# Front-end.net
KiCad netlist of a schematic drawn in Altium Designer
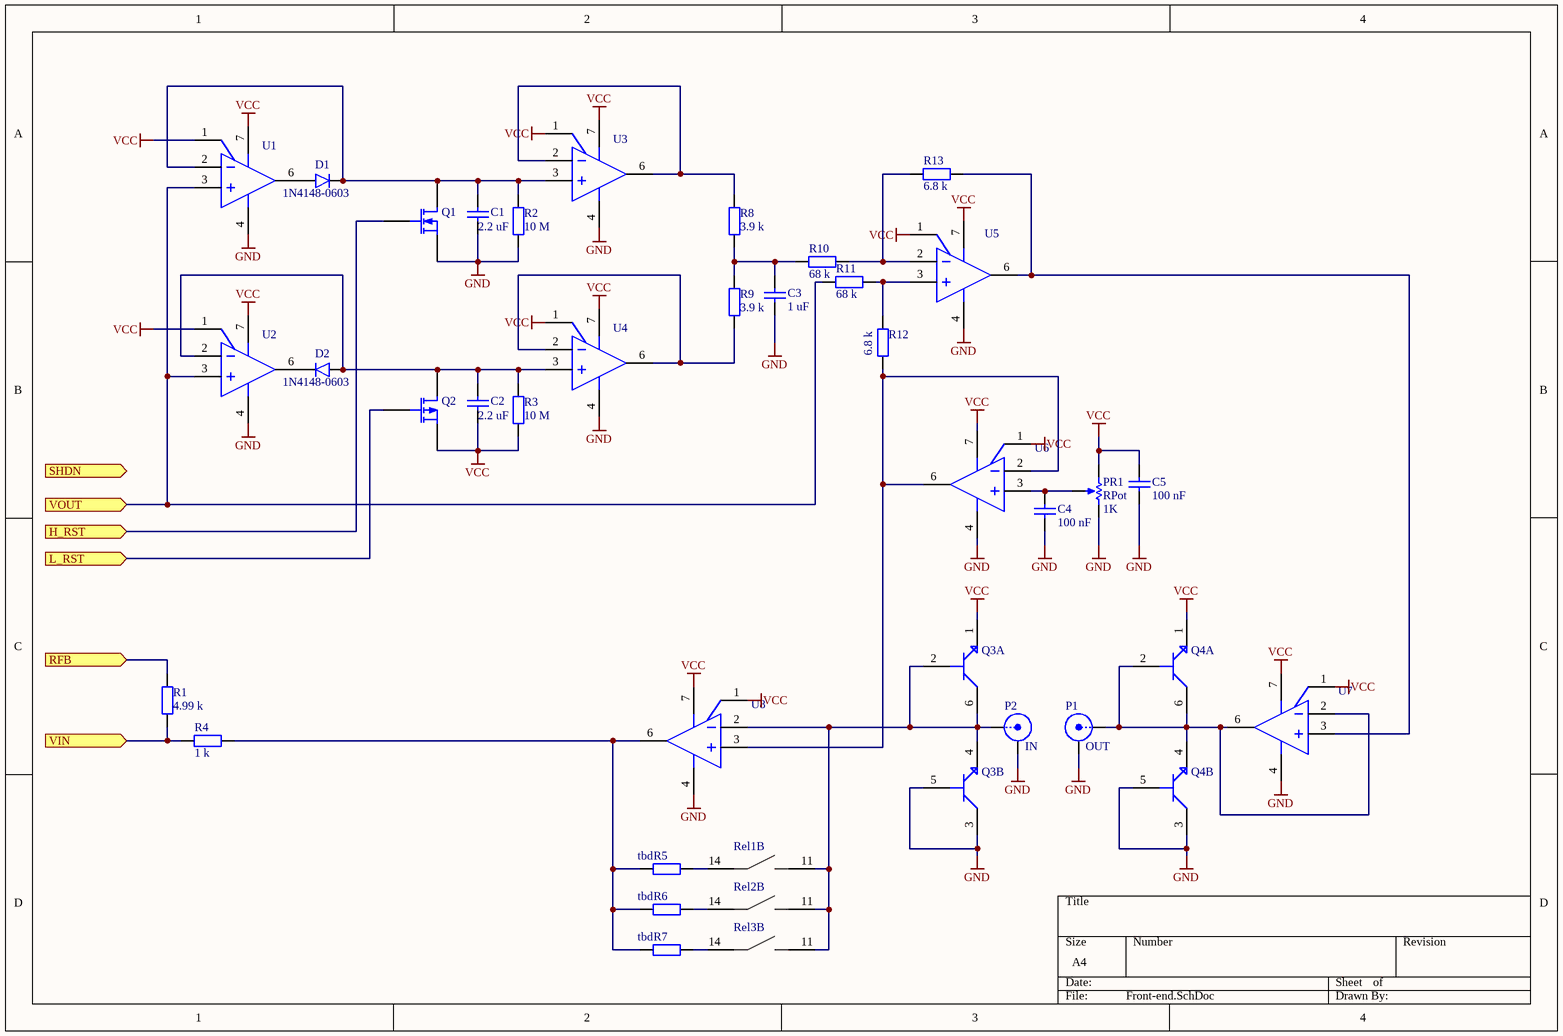
[diagram p0: Front-end.SchDoc]

(export (version "E")
  (design (tool "Eeschema 10.0.6"))
  (components
    (comp (ref "C1")
      (value "2.2 uF")
      (footprint "C1206")
      (description "Capacitor (Semiconductor SIM Model)")
      (fields (field (name "PUBLISHER") "Altium Limited"))
      (libsource (lib "Miscellaneous Devices") (part "Cap Semi"))
    )
    (comp (ref "C2")
      (value "2.2 uF")
      (footprint "C1206")
      (description "Capacitor (Semiconductor SIM Model)")
      (fields (field (name "PUBLISHER") "Altium Limited"))
      (libsource (lib "Miscellaneous Devices") (part "Cap Semi"))
    )
    (comp (ref "C3")
      (value "1 uF")
      (footprint "C1206")
      (description "Capacitor (Semiconductor SIM Model)")
      (fields (field (name "PUBLISHER") "Altium Limited"))
      (libsource (lib "Miscellaneous Devices") (part "Cap Semi"))
    )
    (comp (ref "C4")
      (value "100 nF")
      (footprint "C1206")
      (description "Capacitor (Semiconductor SIM Model)")
      (fields (field (name "PUBLISHER") "Altium Limited"))
      (libsource (lib "Miscellaneous Devices") (part "Cap Semi"))
    )
    (comp (ref "C5")
      (value "100 nF")
      (footprint "C1206")
      (description "Capacitor (Semiconductor SIM Model)")
      (fields (field (name "PUBLISHER") "Altium Limited"))
      (libsource (lib "Miscellaneous Devices") (part "Cap Semi"))
    )
    (comp (ref "D1")
      (value "1N4148-0603")
      (footprint "C1206")
      (description "Dioda: przełączająca; SMD; 100V; 150mA; 4ns; 0603")
      (libsource (lib "Diody") (part "1N4148"))
    )
    (comp (ref "D2")
      (value "1N4148-0603")
      (footprint "C1206")
      (description "Dioda: przełączająca; SMD; 100V; 150mA; 4ns; 0603")
      (libsource (lib "Diody") (part "1N4148"))
    )
    (comp (ref "P1")
      (value "OUT")
      (footprint "BNC_RA")
      (description "BNC Elbow Connector")
      (fields (field (name "PUBLISHER") "Altium Limited"))
      (libsource (lib "Miscellaneous Connectors") (part "BNC"))
    )
    (comp (ref "P2")
      (value "IN")
      (footprint "BNC_RA")
      (description "BNC Elbow Connector")
      (fields (field (name "PUBLISHER") "Altium Limited"))
      (libsource (lib "Miscellaneous Connectors") (part "BNC"))
    )
    (comp (ref "PR1")
      (value "RPot")
      (footprint "TrimmPot")
      (description "Potentiometer")
      (fields (field (name "ALTIUM_VALUE") "1K") (field (name "PUBLISHER") "Altium Limited"))
      (libsource (lib "Miscellaneous Devices") (part "RPot"))
    )
    (comp (ref "Q1")
      (value "MOSFET-N")
      (footprint "E3")
      (description "N-Channel MOSFET")
      (fields (field (name "PUBLISHER") "Altium Limited"))
      (libsource (lib "Miscellaneous Devices") (part "MOSFET-N"))
    )
    (comp (ref "Q2")
      (value "MOSFET-P")
      (footprint "E3")
      (description "P-Channel MOSFET")
      (fields (field (name "PUBLISHER") "Altium Limited"))
      (libsource (lib "Miscellaneous Devices") (part "MOSFET-P"))
    )
    (comp (ref "Q3") (value "MBT3904DW1T1G") (libsource (lib "Schlib1") (part "MBT3904DW1T1G")))
    (comp (ref "Q4") (value "MBT3904DW1T1G") (libsource (lib "Schlib1") (part "MBT3904DW1T1G")))
    (comp (ref "R1")
      (value "4.99 k")
      (footprint "R1206")
      (description "Resistor")
      (fields (field (name "PUBLISHER") "Altium Limited"))
      (libsource (lib "Miscellaneous Devices") (part "Res2"))
    )
    (comp (ref "R2")
      (value "10 M")
      (footprint "R1206")
      (description "Resistor")
      (fields (field (name "PUBLISHER") "Altium Limited"))
      (libsource (lib "Miscellaneous Devices") (part "Res2"))
    )
    (comp (ref "R3")
      (value "10 M")
      (footprint "R1206")
      (description "Resistor")
      (fields (field (name "PUBLISHER") "Altium Limited"))
      (libsource (lib "Miscellaneous Devices") (part "Res2"))
    )
    (comp (ref "R4")
      (value "1 k")
      (footprint "R1206")
      (description "Resistor")
      (fields (field (name "PUBLISHER") "Altium Limited"))
      (libsource (lib "") (part "Res2_1"))
    )
    (comp (ref "R5")
      (value "tbd")
      (footprint "R1206")
      (description "Resistor")
      (fields (field (name "PUBLISHER") "Altium Limited"))
      (libsource (lib "") (part "Res2_1"))
    )
    (comp (ref "R6")
      (value "tbd")
      (footprint "R1206")
      (description "Resistor")
      (fields (field (name "PUBLISHER") "Altium Limited"))
      (libsource (lib "") (part "Res2_1"))
    )
    (comp (ref "R7")
      (value "tbd")
      (footprint "R1206")
      (description "Resistor")
      (fields (field (name "PUBLISHER") "Altium Limited"))
      (libsource (lib "") (part "Res2_1"))
    )
    (comp (ref "R8")
      (value "3.9 k")
      (footprint "R1206")
      (description "Resistor")
      (fields (field (name "PUBLISHER") "Altium Limited"))
      (libsource (lib "Miscellaneous Devices") (part "Res2"))
    )
    (comp (ref "R9")
      (value "3.9 k")
      (footprint "R1206")
      (description "Resistor")
      (fields (field (name "PUBLISHER") "Altium Limited"))
      (libsource (lib "Miscellaneous Devices") (part "Res2"))
    )
    (comp (ref "R10")
      (value "68 k")
      (footprint "R1206")
      (description "Resistor")
      (fields (field (name "PUBLISHER") "Altium Limited"))
      (libsource (lib "") (part "Res2_1"))
    )
    (comp (ref "R11")
      (value "68 k")
      (footprint "R1206")
      (description "Resistor")
      (fields (field (name "PUBLISHER") "Altium Limited"))
      (libsource (lib "") (part "Res2_1"))
    )
    (comp (ref "R12")
      (value "6.8 k")
      (footprint "R1206")
      (description "Resistor")
      (fields (field (name "PUBLISHER") "Altium Limited"))
      (libsource (lib "") (part "Res2_2"))
    )
    (comp (ref "R13")
      (value "6.8 k")
      (footprint "R1206")
      (description "Resistor")
      (fields (field (name "PUBLISHER") "Altium Limited"))
      (libsource (lib "") (part "Res2_1"))
    )
    (comp (ref "Rel1")
      (value "RM45N-3021-85-xxxx")
      (footprint "RM45N-3021-85-xxxx")
      (libsource (lib "Schlib1") (part "RM45N-3021-85-xxxx"))
    )
    (comp (ref "Rel2")
      (value "RM45N-3021-85-xxxx")
      (footprint "RM45N-3021-85-xxxx")
      (libsource (lib "Schlib1") (part "RM45N-3021-85-xxxx"))
    )
    (comp (ref "Rel3")
      (value "RM45N-3021-85-xxxx")
      (footprint "RM45N-3021-85-xxxx")
      (libsource (lib "Schlib1") (part "RM45N-3021-85-xxxx"))
    )
    (comp (ref "U1") (value "MAX4238") (footprint "NSO8_L") (libsource (lib "Schlib1") (part "MAX4298/4299")))
    (comp (ref "U2") (value "MAX4238") (footprint "NSO8_L") (libsource (lib "Schlib1") (part "MAX4298/4299")))
    (comp (ref "U3") (value "MAX4238") (footprint "NSO8_L") (libsource (lib "Schlib1") (part "MAX4298/4299")))
    (comp (ref "U4") (value "MAX4238") (footprint "NSO8_L") (libsource (lib "Schlib1") (part "MAX4298/4299")))
    (comp (ref "U5") (value "MAX4238") (footprint "NSO8_L") (libsource (lib "Schlib1") (part "MAX4298/4299")))
    (comp (ref "U6") (value "MAX4238") (footprint "NSO8_L") (libsource (lib "Schlib1") (part "MAX4298/4299")))
    (comp (ref "U7") (value "MAX4238") (footprint "NSO8_L") (libsource (lib "Schlib1") (part "MAX4298/4299")))
    (comp (ref "U8") (value "MAX4238") (footprint "NSO8_L") (libsource (lib "Schlib1") (part "MAX4298/4299")))
  )
  (nets
    (net (code "1") (name "/H_RST") (class "Default")
      (node (ref "Q1") (pin "2") (pinfunction "G_2") (pintype "passive"))
    )
    (net (code "2") (name "/L_RST") (class "Default")
      (node (ref "Q2") (pin "2") (pinfunction "G_2") (pintype "passive"))
    )
    (net (code "3") (name "/RFB") (class "Default")
      (node (ref "R1") (pin "2") (pinfunction "2_2") (pintype "passive"))
    )
    (net (code "5") (name "/VIN") (class "Default")
      (node (ref "R1") (pin "1") (pinfunction "1_1") (pintype "passive"))
      (node (ref "R4") (pin "2") (pinfunction "2_2") (pintype "passive"))
    )
    (net (code "6") (name "/VOUT") (class "Default")
      (node (ref "R11") (pin "2") (pinfunction "2_2") (pintype "passive"))
      (node (ref "U1") (pin "3") (pinfunction "+_3") (pintype "passive"))
      (node (ref "U2") (pin "3") (pinfunction "+_3") (pintype "passive"))
    )
    (net (code "7") (name "GND") (class "Default")
      (node (ref "C1") (pin "1") (pinfunction "1_1") (pintype "passive"))
      (node (ref "C3") (pin "1") (pinfunction "1_1") (pintype "passive"))
      (node (ref "C4") (pin "1") (pinfunction "1_1") (pintype "passive"))
      (node (ref "C5") (pin "1") (pinfunction "1_1") (pintype "passive"))
      (node (ref "P1") (pin "2") (pinfunction "Y_2") (pintype "passive"))
      (node (ref "P2") (pin "2") (pinfunction "Y_2") (pintype "passive"))
      (node (ref "PR1") (pin "2") (pinfunction "BOT_2") (pintype "passive"))
      (node (ref "Q1") (pin "3") (pinfunction "S_3") (pintype "passive"))
      (node (ref "Q3") (pin "3") (pinfunction "3_3") (pintype "passive"))
      (node (ref "Q3") (pin "5") (pinfunction "5_5") (pintype "passive"))
      (node (ref "Q4") (pin "3") (pinfunction "3_3") (pintype "passive"))
      (node (ref "Q4") (pin "5") (pinfunction "5_5") (pintype "passive"))
      (node (ref "R2") (pin "1") (pinfunction "1_1") (pintype "passive"))
      (node (ref "U1") (pin "4") (pintype "passive"))
      (node (ref "U2") (pin "4") (pintype "passive"))
      (node (ref "U3") (pin "4") (pintype "passive"))
      (node (ref "U4") (pin "4") (pintype "passive"))
      (node (ref "U5") (pin "4") (pintype "passive"))
      (node (ref "U6") (pin "4") (pintype "passive"))
      (node (ref "U7") (pin "4") (pintype "passive"))
      (node (ref "U8") (pin "4") (pintype "passive"))
    )
    (net (code "8") (name "Net-(C3-Pad2)") (class "Default")
      (node (ref "C3") (pin "2") (pinfunction "2_2") (pintype "passive"))
      (node (ref "R10") (pin "2") (pinfunction "2_2") (pintype "passive"))
      (node (ref "R8") (pin "1") (pinfunction "1_1") (pintype "passive"))
      (node (ref "R9") (pin "2") (pinfunction "2_2") (pintype "passive"))
    )
    (net (code "9") (name "Net-(D1-Pad2)") (class "Default")
      (node (ref "D1") (pin "2") (pinfunction "2_2") (pintype "passive"))
      (node (ref "U1") (pin "6") (pintype "passive"))
    )
    (net (code "10") (name "Net-(D2-Pad1)") (class "Default")
      (node (ref "D2") (pin "1") (pinfunction "1_1") (pintype "passive"))
      (node (ref "U2") (pin "6") (pintype "passive"))
    )
    (net (code "11") (name "Net-(P1-X)") (class "Default")
      (node (ref "P1") (pin "1") (pinfunction "X_1") (pintype "passive"))
      (node (ref "Q4") (pin "2") (pinfunction "2_2") (pintype "passive"))
      (node (ref "Q4") (pin "4") (pinfunction "4_4") (pintype "passive"))
      (node (ref "Q4") (pin "6") (pinfunction "2_6") (pintype "passive"))
      (node (ref "U7") (pin "2") (pinfunction "-_2") (pintype "passive"))
      (node (ref "U7") (pin "6") (pintype "passive"))
    )
    (net (code "12") (name "Net-(P2-X)") (class "Default")
      (node (ref "P2") (pin "1") (pinfunction "X_1") (pintype "passive"))
      (node (ref "Q3") (pin "2") (pinfunction "2_2") (pintype "passive"))
      (node (ref "Q3") (pin "4") (pinfunction "4_4") (pintype "passive"))
      (node (ref "Q3") (pin "6") (pinfunction "2_6") (pintype "passive"))
      (node (ref "Rel1") (pin "11") (pinfunction "SW_11") (pintype "passive"))
      (node (ref "Rel2") (pin "11") (pinfunction "SW_11") (pintype "passive"))
      (node (ref "Rel3") (pin "11") (pinfunction "SW_11") (pintype "passive"))
      (node (ref "U8") (pin "2") (pinfunction "-_2") (pintype "passive"))
    )
    (net (code "13") (name "Net-(PR1-TAP)") (class "Default")
      (node (ref "C4") (pin "2") (pinfunction "2_2") (pintype "passive"))
      (node (ref "PR1") (pin "3") (pinfunction "TAP_3") (pintype "passive"))
      (node (ref "U6") (pin "3") (pinfunction "+_3") (pintype "passive"))
    )
    (net (code "14") (name "Net-(Q1-D)") (class "Default")
      (node (ref "C1") (pin "2") (pinfunction "2_2") (pintype "passive"))
      (node (ref "D1") (pin "1") (pinfunction "1_1") (pintype "passive"))
      (node (ref "Q1") (pin "1") (pinfunction "D_1") (pintype "passive"))
      (node (ref "R2") (pin "2") (pinfunction "2_2") (pintype "passive"))
      (node (ref "U1") (pin "2") (pinfunction "-_2") (pintype "passive"))
      (node (ref "U3") (pin "3") (pinfunction "+_3") (pintype "passive"))
    )
    (net (code "15") (name "Net-(Q2-D)") (class "Default")
      (node (ref "C2") (pin "2") (pinfunction "2_2") (pintype "passive"))
      (node (ref "D2") (pin "2") (pinfunction "2_2") (pintype "passive"))
      (node (ref "Q2") (pin "1") (pinfunction "D_1") (pintype "passive"))
      (node (ref "R3") (pin "2") (pinfunction "2_2") (pintype "passive"))
      (node (ref "U2") (pin "2") (pinfunction "-_2") (pintype "passive"))
      (node (ref "U4") (pin "3") (pinfunction "+_3") (pintype "passive"))
    )
    (net (code "16") (name "Net-(R4-Pad1)") (class "Default")
      (node (ref "R4") (pin "1") (pinfunction "1_1") (pintype "passive"))
      (node (ref "R5") (pin "2") (pinfunction "2_2") (pintype "passive"))
      (node (ref "R6") (pin "2") (pinfunction "2_2") (pintype "passive"))
      (node (ref "R7") (pin "2") (pinfunction "2_2") (pintype "passive"))
      (node (ref "U8") (pin "6") (pintype "passive"))
    )
    (net (code "17") (name "Net-(R5-Pad1)") (class "Default")
      (node (ref "R5") (pin "1") (pinfunction "1_1") (pintype "passive"))
      (node (ref "Rel1") (pin "14") (pinfunction "SW_14") (pintype "passive"))
    )
    (net (code "18") (name "Net-(R6-Pad1)") (class "Default")
      (node (ref "R6") (pin "1") (pinfunction "1_1") (pintype "passive"))
      (node (ref "Rel2") (pin "14") (pinfunction "SW_14") (pintype "passive"))
    )
    (net (code "19") (name "Net-(R7-Pad1)") (class "Default")
      (node (ref "R7") (pin "1") (pinfunction "1_1") (pintype "passive"))
      (node (ref "Rel3") (pin "14") (pinfunction "SW_14") (pintype "passive"))
    )
    (net (code "20") (name "Net-(U3--)") (class "Default")
      (node (ref "R8") (pin "2") (pinfunction "2_2") (pintype "passive"))
      (node (ref "U3") (pin "2") (pinfunction "-_2") (pintype "passive"))
      (node (ref "U3") (pin "6") (pintype "passive"))
    )
    (net (code "21") (name "Net-(U4--)") (class "Default")
      (node (ref "R9") (pin "1") (pinfunction "1_1") (pintype "passive"))
      (node (ref "U4") (pin "2") (pinfunction "-_2") (pintype "passive"))
      (node (ref "U4") (pin "6") (pintype "passive"))
    )
    (net (code "22") (name "Net-(U5-+)") (class "Default")
      (node (ref "R11") (pin "1") (pinfunction "1_1") (pintype "passive"))
      (node (ref "R12") (pin "1") (pinfunction "1_1") (pintype "passive"))
      (node (ref "U5") (pin "3") (pinfunction "+_3") (pintype "passive"))
    )
    (net (code "23") (name "Net-(U5--)") (class "Default")
      (node (ref "R10") (pin "1") (pinfunction "1_1") (pintype "passive"))
      (node (ref "R13") (pin "2") (pinfunction "2_2") (pintype "passive"))
      (node (ref "U5") (pin "2") (pinfunction "-_2") (pintype "passive"))
    )
    (net (code "24") (name "Net-(U6--)") (class "Default")
      (node (ref "R12") (pin "2") (pinfunction "2_2") (pintype "passive"))
      (node (ref "U6") (pin "2") (pinfunction "-_2") (pintype "passive"))
      (node (ref "U6") (pin "6") (pintype "passive"))
      (node (ref "U8") (pin "3") (pinfunction "+_3") (pintype "passive"))
    )
    (net (code "25") (name "Net-(U7-+)") (class "Default")
      (node (ref "R13") (pin "1") (pinfunction "1_1") (pintype "passive"))
      (node (ref "U5") (pin "6") (pintype "passive"))
      (node (ref "U7") (pin "3") (pinfunction "+_3") (pintype "passive"))
    )
    (net (code "26") (name "VCC") (class "Default")
      (node (ref "C2") (pin "1") (pinfunction "1_1") (pintype "passive"))
      (node (ref "C5") (pin "2") (pinfunction "2_2") (pintype "passive"))
      (node (ref "PR1") (pin "1") (pinfunction "TOP_1") (pintype "passive"))
      (node (ref "Q2") (pin "3") (pinfunction "S_3") (pintype "passive"))
      (node (ref "Q3") (pin "1") (pinfunction "1_1") (pintype "passive"))
      (node (ref "Q4") (pin "1") (pinfunction "1_1") (pintype "passive"))
      (node (ref "R3") (pin "1") (pinfunction "1_1") (pintype "passive"))
      (node (ref "U1") (pin "1") (pinfunction "SHDN_1") (pintype "passive"))
      (node (ref "U1") (pin "7") (pintype "passive"))
      (node (ref "U2") (pin "1") (pinfunction "SHDN_1") (pintype "passive"))
      (node (ref "U2") (pin "7") (pintype "passive"))
      (node (ref "U3") (pin "1") (pinfunction "SHDN_1") (pintype "passive"))
      (node (ref "U3") (pin "7") (pintype "passive"))
      (node (ref "U4") (pin "1") (pinfunction "SHDN_1") (pintype "passive"))
      (node (ref "U4") (pin "7") (pintype "passive"))
      (node (ref "U5") (pin "1") (pinfunction "SHDN_1") (pintype "passive"))
      (node (ref "U5") (pin "7") (pintype "passive"))
      (node (ref "U6") (pin "1") (pinfunction "SHDN_1") (pintype "passive"))
      (node (ref "U6") (pin "7") (pintype "passive"))
      (node (ref "U7") (pin "1") (pinfunction "SHDN_1") (pintype "passive"))
      (node (ref "U7") (pin "7") (pintype "passive"))
      (node (ref "U8") (pin "1") (pinfunction "SHDN_1") (pintype "passive"))
      (node (ref "U8") (pin "7") (pintype "passive"))
    )
  )
)
